# srvg-001.net
KiCad netlist of a schematic drawn in EAGLE
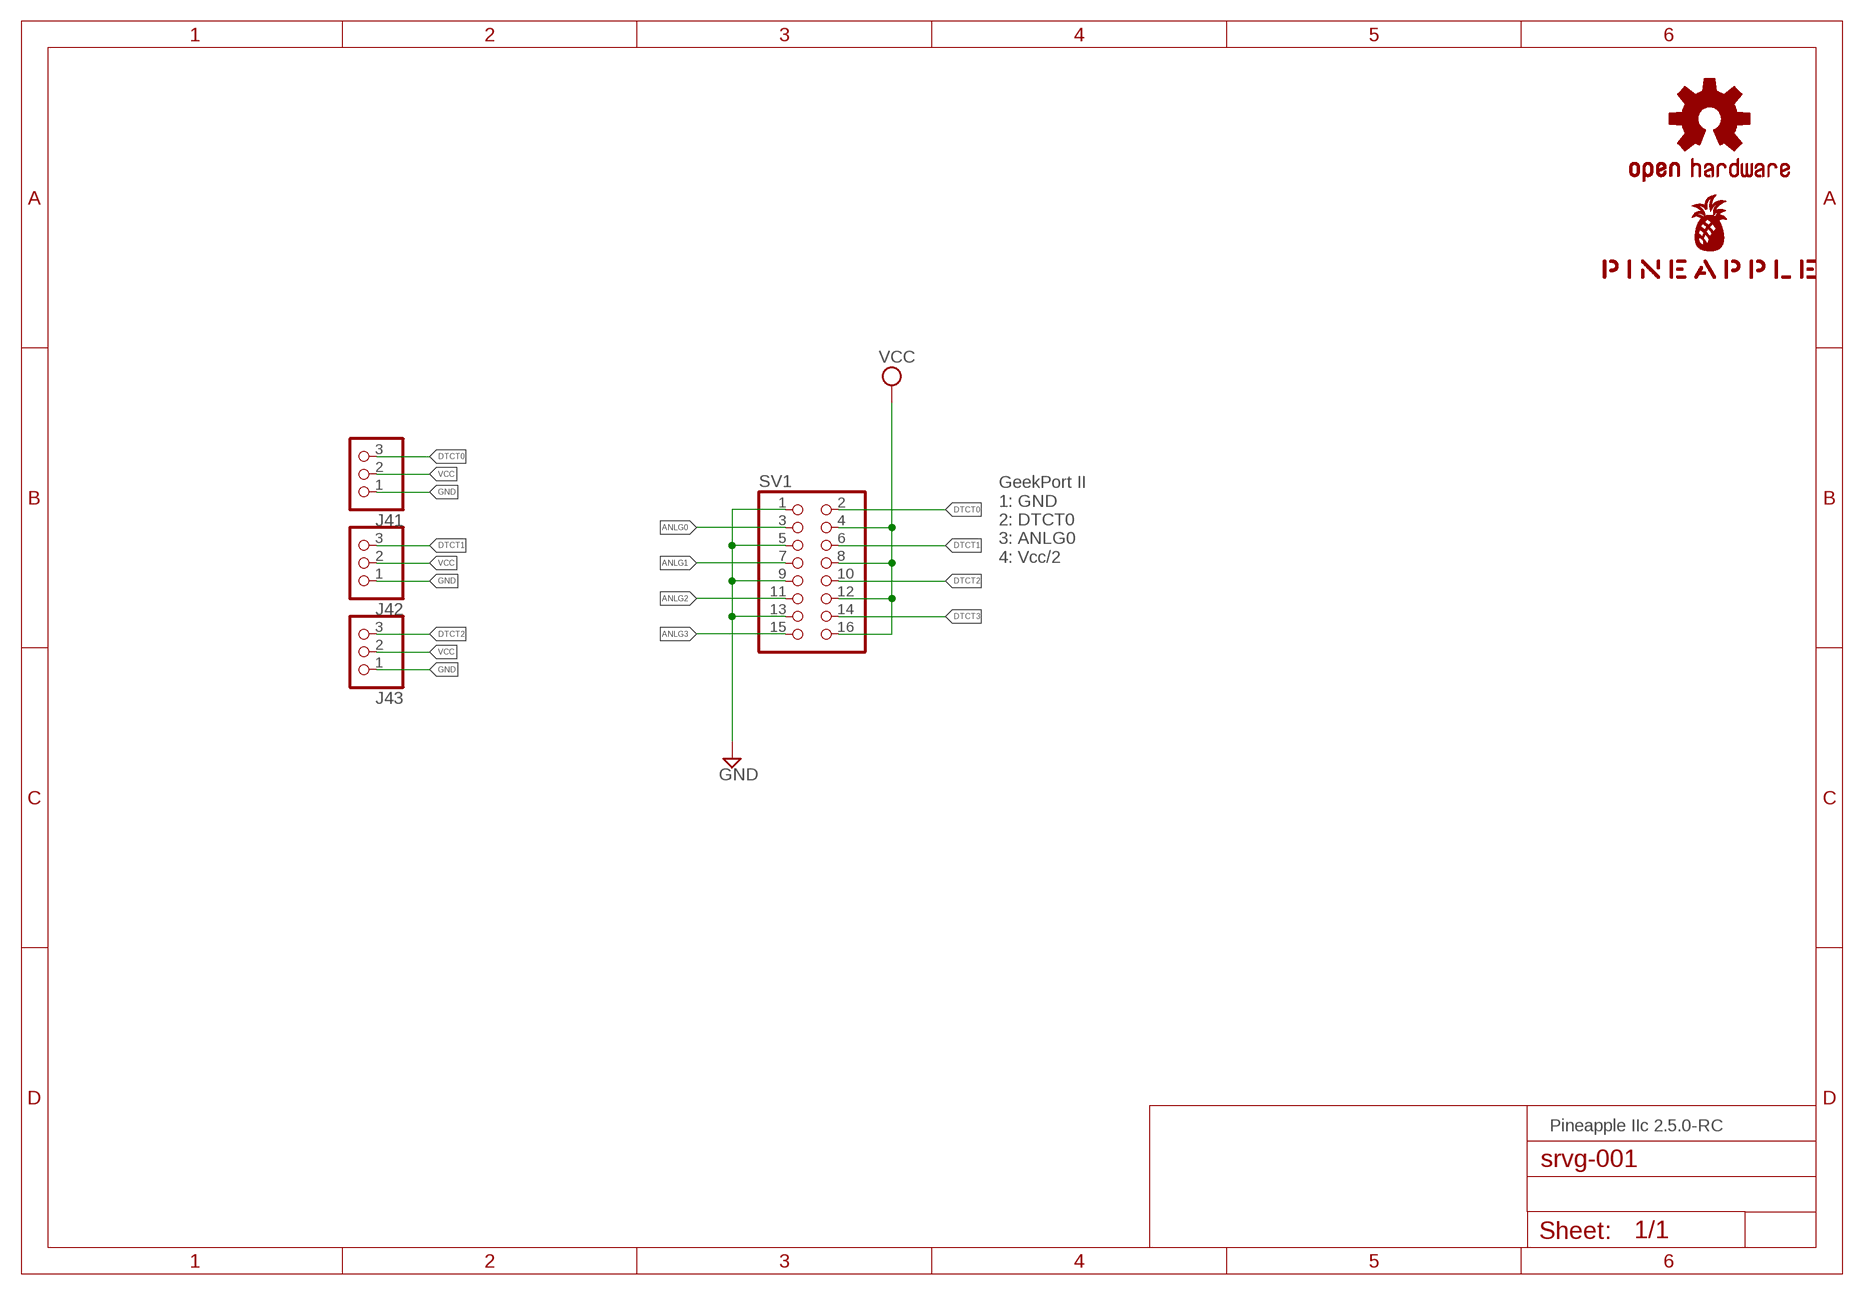
[diagram p0: schematic, sheet 1]

(export (version "E")
  (design (tool "Eeschema 10.0.6"))
  (components
    (comp (ref "J41")
      (value "PINHD-1X3")
      (footprint "eagle-import:1X03")
      (libsource (lib "eagle-import") (part "PINHD-1X3"))
    )
    (comp (ref "J42")
      (value "PINHD-1X3")
      (footprint "eagle-import:1X03")
      (libsource (lib "eagle-import") (part "PINHD-1X3"))
    )
    (comp (ref "J43")
      (value "PINHD-1X3")
      (footprint "eagle-import:1X03")
      (libsource (lib "eagle-import") (part "PINHD-1X3"))
    )
    (comp (ref "LOGO1")
      (value "OSHW-LOGOS-COPPER")
      (footprint "eagle-import:OSHW-LOGO-S_COPPER")
      (libsource (lib "eagle-import") (part "OSHW-LOGOS-COPPER"))
    )
    (comp (ref "SV1")
      (value "PINHD-2X8")
      (footprint "eagle-import:2X08")
      (libsource (lib "eagle-import") (part "PINHD-2X8"))
    )
    (comp (ref "U$1")
      (value "PINEAPPLE450_SILK")
      (footprint "eagle-import:PINEAPPLE450_SILK")
      (libsource (lib "eagle-import") (part "PINEAPPLE450_SILK"))
    )
  )
  (nets
    (net (code "1") (name "ANLG0") (class "Default")
      (node (ref "SV1") (pin "3") (pinfunction "3_3") (pintype "passive"))
    )
    (net (code "2") (name "ANLG1") (class "Default")
      (node (ref "SV1") (pin "7") (pinfunction "7_7") (pintype "passive"))
    )
    (net (code "3") (name "ANLG2") (class "Default")
      (node (ref "SV1") (pin "11") (pinfunction "11_11") (pintype "passive"))
    )
    (net (code "4") (name "ANLG3") (class "Default")
      (node (ref "SV1") (pin "15") (pinfunction "15_15") (pintype "passive"))
    )
    (net (code "5") (name "DTCT0") (class "Default")
      (node (ref "J41") (pin "3") (pinfunction "3_3") (pintype "passive"))
      (node (ref "SV1") (pin "2") (pinfunction "2_2") (pintype "passive"))
    )
    (net (code "6") (name "DTCT1") (class "Default")
      (node (ref "J42") (pin "3") (pinfunction "3_3") (pintype "passive"))
      (node (ref "SV1") (pin "6") (pinfunction "6_6") (pintype "passive"))
    )
    (net (code "7") (name "DTCT2") (class "Default")
      (node (ref "J43") (pin "3") (pinfunction "3_3") (pintype "passive"))
      (node (ref "SV1") (pin "10") (pinfunction "10_10") (pintype "passive"))
    )
    (net (code "8") (name "DTCT3") (class "Default")
      (node (ref "SV1") (pin "14") (pinfunction "14_14") (pintype "passive"))
    )
    (net (code "9") (name "GND") (class "Default")
      (node (ref "J41") (pin "1") (pinfunction "1_1") (pintype "passive"))
      (node (ref "J42") (pin "1") (pinfunction "1_1") (pintype "passive"))
      (node (ref "J43") (pin "1") (pinfunction "1_1") (pintype "passive"))
      (node (ref "SV1") (pin "1") (pinfunction "1_1") (pintype "passive"))
      (node (ref "SV1") (pin "13") (pinfunction "13_13") (pintype "passive"))
      (node (ref "SV1") (pin "5") (pinfunction "5_5") (pintype "passive"))
      (node (ref "SV1") (pin "9") (pinfunction "9_9") (pintype "passive"))
    )
    (net (code "10") (name "VCC") (class "Default")
      (node (ref "J41") (pin "2") (pinfunction "2_2") (pintype "passive"))
      (node (ref "J42") (pin "2") (pinfunction "2_2") (pintype "passive"))
      (node (ref "J43") (pin "2") (pinfunction "2_2") (pintype "passive"))
      (node (ref "SV1") (pin "12") (pinfunction "12_12") (pintype "passive"))
      (node (ref "SV1") (pin "16") (pinfunction "16_16") (pintype "passive"))
      (node (ref "SV1") (pin "4") (pinfunction "4_4") (pintype "passive"))
      (node (ref "SV1") (pin "8") (pinfunction "8_8") (pintype "passive"))
    )
  )
)
